# Multiplexers.net
KiCad netlist of a schematic drawn in Altium Designer
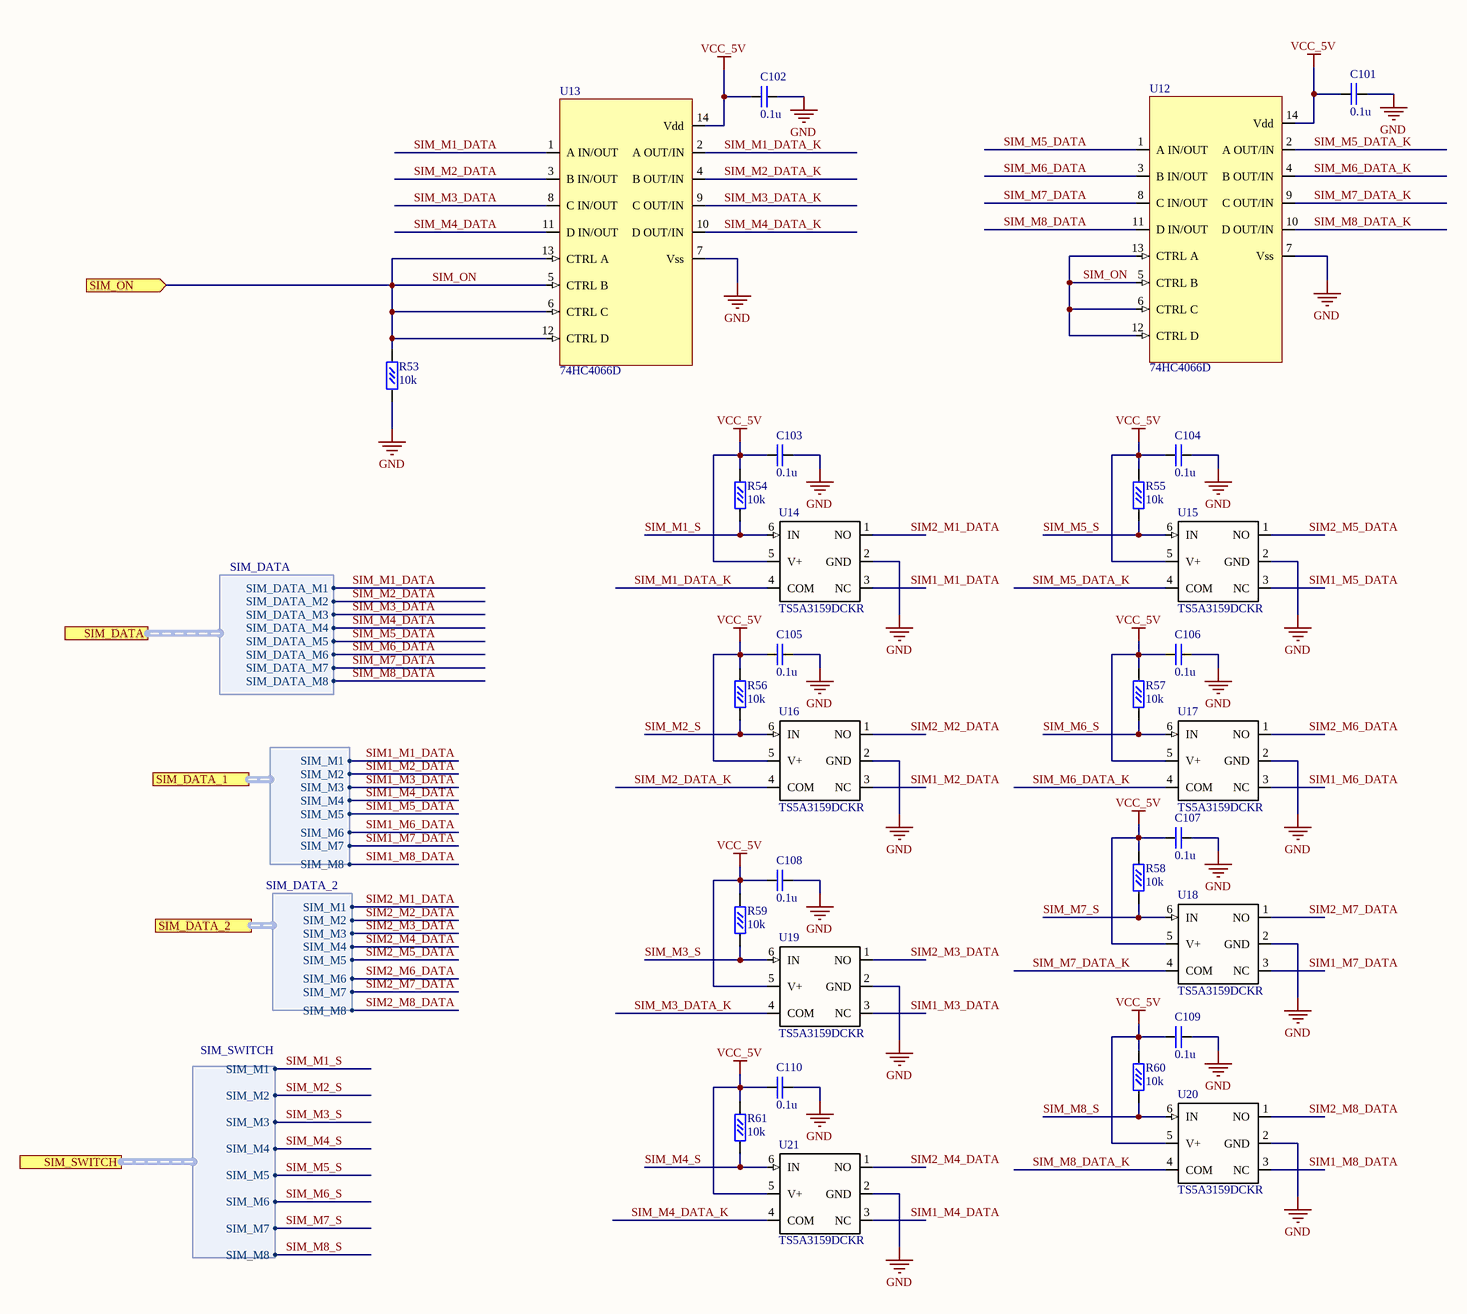
[diagram p0: Multiplexers.SchDoc]

(export (version "E")
  (design (tool "Eeschema 10.0.6"))
  (components
    (comp (ref "C101")
      (value "0.1u")
      (footprint "C0402")
      (description "Chip Capacitor 0402")
      (fields (field (name "VOLTAGE") "16В") (field (name "TOLERANCE") "10%"))
      (libsource (lib "Passives") (part "C0402"))
    )
    (comp (ref "C102")
      (value "0.1u")
      (footprint "C0402")
      (description "Chip Capacitor 0402")
      (fields (field (name "VOLTAGE") "16В") (field (name "TOLERANCE") "10%"))
      (libsource (lib "Passives") (part "C0402"))
    )
    (comp (ref "C103")
      (value "0.1u")
      (footprint "SMD_components:C0402")
      (description "Chip Capacitor 0402")
      (fields (field (name "VOLTAGE") "25В") (field (name "TOLERANCE") "10%"))
      (libsource (lib "Passives") (part "C0402"))
    )
    (comp (ref "C104")
      (value "0.1u")
      (footprint "SMD_components:C0402")
      (description "Chip Capacitor 0402")
      (fields (field (name "VOLTAGE") "25В") (field (name "TOLERANCE") "10%"))
      (libsource (lib "Passives") (part "C0402"))
    )
    (comp (ref "C105")
      (value "0.1u")
      (footprint "SMD_components:C0402")
      (description "Chip Capacitor 0402")
      (fields (field (name "VOLTAGE") "25В") (field (name "TOLERANCE") "10%"))
      (libsource (lib "Passives") (part "C0402"))
    )
    (comp (ref "C106")
      (value "0.1u")
      (footprint "SMD_components:C0402")
      (description "Chip Capacitor 0402")
      (fields (field (name "VOLTAGE") "25В") (field (name "TOLERANCE") "10%"))
      (libsource (lib "Passives") (part "C0402"))
    )
    (comp (ref "C107")
      (value "0.1u")
      (footprint "SMD_components:C0402")
      (description "Chip Capacitor 0402")
      (fields (field (name "VOLTAGE") "25В") (field (name "TOLERANCE") "10%"))
      (libsource (lib "Passives") (part "C0402"))
    )
    (comp (ref "C108")
      (value "0.1u")
      (footprint "SMD_components:C0402")
      (description "Chip Capacitor 0402")
      (fields (field (name "VOLTAGE") "25В") (field (name "TOLERANCE") "10%"))
      (libsource (lib "Passives") (part "C0402"))
    )
    (comp (ref "C109")
      (value "0.1u")
      (footprint "SMD_components:C0402")
      (description "Chip Capacitor 0402")
      (fields (field (name "VOLTAGE") "25В") (field (name "TOLERANCE") "10%"))
      (libsource (lib "Passives") (part "C0402"))
    )
    (comp (ref "C110")
      (value "0.1u")
      (footprint "SMD_components:C0402")
      (description "Chip Capacitor 0402")
      (fields (field (name "VOLTAGE") "25В") (field (name "TOLERANCE") "10%"))
      (libsource (lib "Passives") (part "C0402"))
    )
    (comp (ref "R53")
      (value "10k")
      (footprint "R0603")
      (description "Chip Resistor 0603, 0.1 W")
      (fields (field (name "POWER") "0.1Вт") (field (name "TOLERANCE") "1%"))
      (libsource (lib "Passives") (part "R0603_0.1"))
    )
    (comp (ref "R54")
      (value "10k")
      (footprint "SMD_components:R0603")
      (description "Chip Resistor 0603, 0.1 W")
      (fields (field (name "POWER") "0.1Вт") (field (name "TOLERANCE") "1%"))
      (libsource (lib "Passives") (part "R0603_0.1"))
    )
    (comp (ref "R55")
      (value "10k")
      (footprint "SMD_components:R0603")
      (description "Chip Resistor 0603, 0.1 W")
      (fields (field (name "POWER") "0.1Вт") (field (name "TOLERANCE") "1%"))
      (libsource (lib "Passives") (part "R0603_0.1"))
    )
    (comp (ref "R56")
      (value "10k")
      (footprint "SMD_components:R0603")
      (description "Chip Resistor 0603, 0.1 W")
      (fields (field (name "POWER") "0.1Вт") (field (name "TOLERANCE") "1%"))
      (libsource (lib "Passives") (part "R0603_0.1"))
    )
    (comp (ref "R57")
      (value "10k")
      (footprint "SMD_components:R0603")
      (description "Chip Resistor 0603, 0.1 W")
      (fields (field (name "POWER") "0.1Вт") (field (name "TOLERANCE") "1%"))
      (libsource (lib "Passives") (part "R0603_0.1"))
    )
    (comp (ref "R58")
      (value "10k")
      (footprint "SMD_components:R0603")
      (description "Chip Resistor 0603, 0.1 W")
      (fields (field (name "POWER") "0.1Вт") (field (name "TOLERANCE") "1%"))
      (libsource (lib "Passives") (part "R0603_0.1"))
    )
    (comp (ref "R59")
      (value "10k")
      (footprint "SMD_components:R0603")
      (description "Chip Resistor 0603, 0.1 W")
      (fields (field (name "POWER") "0.1Вт") (field (name "TOLERANCE") "1%"))
      (libsource (lib "Passives") (part "R0603_0.1"))
    )
    (comp (ref "R60")
      (value "10k")
      (footprint "SMD_components:R0603")
      (description "Chip Resistor 0603, 0.1 W")
      (fields (field (name "POWER") "0.1Вт") (field (name "TOLERANCE") "1%"))
      (libsource (lib "Passives") (part "R0603_0.1"))
    )
    (comp (ref "R61")
      (value "10k")
      (footprint "SMD_components:R0603")
      (description "Chip Resistor 0603, 0.1 W")
      (fields (field (name "POWER") "0.1Вт") (field (name "TOLERANCE") "1%"))
      (libsource (lib "Passives") (part "R0603_0.1"))
    )
    (comp (ref "U12")
      (value "74HC4066D")
      (footprint "14-SOIC")
      (description "CMOS QUAD BILATERAL SWITCH")
      (fields (field (name "MANUFACTURER") "Nexperia"))
      (libsource (lib "IC") (part "74HC4066D"))
    )
    (comp (ref "U13")
      (value "74HC4066D")
      (footprint "14-SOIC")
      (description "CMOS QUAD BILATERAL SWITCH")
      (fields (field (name "MANUFACTURER") "Nexperia"))
      (libsource (lib "IC") (part "74HC4066D"))
    )
    (comp (ref "U14")
      (value "TS5A3159")
      (footprint "SC70-6")
      (description "Analog SPDT Switch")
      (fields (field (name "MANUFACTURER") "Texas Instruments") (field (name "PARTNUMBER") "TS5A3159DCKR"))
      (libsource (lib "IC") (part "TS5A3159"))
    )
    (comp (ref "U15")
      (value "TS5A3159")
      (footprint "SC70-6")
      (description "Analog SPDT Switch")
      (fields (field (name "MANUFACTURER") "Texas Instruments") (field (name "PARTNUMBER") "TS5A3159DCKR"))
      (libsource (lib "IC") (part "TS5A3159"))
    )
    (comp (ref "U16")
      (value "TS5A3159")
      (footprint "SC70-6")
      (description "Analog SPDT Switch")
      (fields (field (name "MANUFACTURER") "Texas Instruments") (field (name "PARTNUMBER") "TS5A3159DCKR"))
      (libsource (lib "IC") (part "TS5A3159"))
    )
    (comp (ref "U17")
      (value "TS5A3159")
      (footprint "SC70-6")
      (description "Analog SPDT Switch")
      (fields (field (name "MANUFACTURER") "Texas Instruments") (field (name "PARTNUMBER") "TS5A3159DCKR"))
      (libsource (lib "IC") (part "TS5A3159"))
    )
    (comp (ref "U18")
      (value "TS5A3159")
      (footprint "SC70-6")
      (description "Analog SPDT Switch")
      (fields (field (name "MANUFACTURER") "Texas Instruments") (field (name "PARTNUMBER") "TS5A3159DCKR"))
      (libsource (lib "IC") (part "TS5A3159"))
    )
    (comp (ref "U19")
      (value "TS5A3159")
      (footprint "SC70-6")
      (description "Analog SPDT Switch")
      (fields (field (name "MANUFACTURER") "Texas Instruments") (field (name "PARTNUMBER") "TS5A3159DCKR"))
      (libsource (lib "IC") (part "TS5A3159"))
    )
    (comp (ref "U20")
      (value "TS5A3159")
      (footprint "SC70-6")
      (description "Analog SPDT Switch")
      (fields (field (name "MANUFACTURER") "Texas Instruments") (field (name "PARTNUMBER") "TS5A3159DCKR"))
      (libsource (lib "IC") (part "TS5A3159"))
    )
    (comp (ref "U21")
      (value "TS5A3159")
      (footprint "SC70-6")
      (description "Analog SPDT Switch")
      (fields (field (name "MANUFACTURER") "Texas Instruments") (field (name "PARTNUMBER") "TS5A3159DCKR"))
      (libsource (lib "IC") (part "TS5A3159"))
    )
  )
  (nets
    (net (code "5") (name "/SIM1_M1_DATA") (class "Default")
      (node (ref "U14") (pin "3") (pinfunction "NC_3") (pintype "passive"))
    )
    (net (code "6") (name "/SIM1_M2_DATA") (class "Default")
      (node (ref "U16") (pin "3") (pinfunction "NC_3") (pintype "passive"))
    )
    (net (code "7") (name "/SIM1_M3_DATA") (class "Default")
      (node (ref "U19") (pin "3") (pinfunction "NC_3") (pintype "passive"))
    )
    (net (code "8") (name "/SIM1_M4_DATA") (class "Default")
      (node (ref "U21") (pin "3") (pinfunction "NC_3") (pintype "passive"))
    )
    (net (code "9") (name "/SIM1_M5_DATA") (class "Default")
      (node (ref "U15") (pin "3") (pinfunction "NC_3") (pintype "passive"))
    )
    (net (code "10") (name "/SIM1_M6_DATA") (class "Default")
      (node (ref "U17") (pin "3") (pinfunction "NC_3") (pintype "passive"))
    )
    (net (code "11") (name "/SIM1_M7_DATA") (class "Default")
      (node (ref "U18") (pin "3") (pinfunction "NC_3") (pintype "passive"))
    )
    (net (code "12") (name "/SIM1_M8_DATA") (class "Default")
      (node (ref "U20") (pin "3") (pinfunction "NC_3") (pintype "passive"))
    )
    (net (code "13") (name "/SIM2_M1_DATA") (class "Default")
      (node (ref "U14") (pin "1") (pinfunction "NO_1") (pintype "passive"))
    )
    (net (code "14") (name "/SIM2_M2_DATA") (class "Default")
      (node (ref "U16") (pin "1") (pinfunction "NO_1") (pintype "passive"))
    )
    (net (code "15") (name "/SIM2_M3_DATA") (class "Default")
      (node (ref "U19") (pin "1") (pinfunction "NO_1") (pintype "passive"))
    )
    (net (code "16") (name "/SIM2_M4_DATA") (class "Default")
      (node (ref "U21") (pin "1") (pinfunction "NO_1") (pintype "passive"))
    )
    (net (code "17") (name "/SIM2_M5_DATA") (class "Default")
      (node (ref "U15") (pin "1") (pinfunction "NO_1") (pintype "passive"))
    )
    (net (code "18") (name "/SIM2_M6_DATA") (class "Default")
      (node (ref "U17") (pin "1") (pinfunction "NO_1") (pintype "passive"))
    )
    (net (code "19") (name "/SIM2_M7_DATA") (class "Default")
      (node (ref "U18") (pin "1") (pinfunction "NO_1") (pintype "passive"))
    )
    (net (code "20") (name "/SIM2_M8_DATA") (class "Default")
      (node (ref "U20") (pin "1") (pinfunction "NO_1") (pintype "passive"))
    )
    (net (code "21") (name "/SIM_M1_DATA") (class "Default")
      (node (ref "U13") (pin "1") (pinfunction "A_IN/OUT_1") (pintype "bidirectional"))
    )
    (net (code "22") (name "/SIM_M1_DATA_K") (class "Default")
      (node (ref "U13") (pin "2") (pinfunction "A_OUT/IN_2") (pintype "bidirectional"))
      (node (ref "U14") (pin "4") (pinfunction "COM_4") (pintype "passive"))
    )
    (net (code "23") (name "/SIM_M1_S") (class "Default")
      (node (ref "R54") (pin "1") (pinfunction "1_1") (pintype "passive"))
      (node (ref "U14") (pin "6") (pinfunction "IN_6") (pintype "input"))
    )
    (net (code "24") (name "/SIM_M2_DATA") (class "Default")
      (node (ref "U13") (pin "3") (pinfunction "B_IN/OUT_3") (pintype "bidirectional"))
    )
    (net (code "25") (name "/SIM_M2_DATA_K") (class "Default")
      (node (ref "U13") (pin "4") (pinfunction "B_OUT/IN_4") (pintype "bidirectional"))
      (node (ref "U16") (pin "4") (pinfunction "COM_4") (pintype "passive"))
    )
    (net (code "26") (name "/SIM_M2_S") (class "Default")
      (node (ref "R56") (pin "1") (pinfunction "1_1") (pintype "passive"))
      (node (ref "U16") (pin "6") (pinfunction "IN_6") (pintype "input"))
    )
    (net (code "27") (name "/SIM_M3_DATA") (class "Default")
      (node (ref "U13") (pin "8") (pinfunction "C_IN/OUT_8") (pintype "bidirectional"))
    )
    (net (code "28") (name "/SIM_M3_DATA_K") (class "Default")
      (node (ref "U13") (pin "9") (pinfunction "C_OUT/IN_9") (pintype "bidirectional"))
      (node (ref "U19") (pin "4") (pinfunction "COM_4") (pintype "passive"))
    )
    (net (code "29") (name "/SIM_M3_S") (class "Default")
      (node (ref "R59") (pin "1") (pinfunction "1_1") (pintype "passive"))
      (node (ref "U19") (pin "6") (pinfunction "IN_6") (pintype "input"))
    )
    (net (code "30") (name "/SIM_M4_DATA") (class "Default")
      (node (ref "U13") (pin "11") (pinfunction "D_IN/OUT_11") (pintype "bidirectional"))
    )
    (net (code "31") (name "/SIM_M4_DATA_K") (class "Default")
      (node (ref "U13") (pin "10") (pinfunction "D_OUT/IN_10") (pintype "bidirectional"))
      (node (ref "U21") (pin "4") (pinfunction "COM_4") (pintype "passive"))
    )
    (net (code "32") (name "/SIM_M4_S") (class "Default")
      (node (ref "R61") (pin "1") (pinfunction "1_1") (pintype "passive"))
      (node (ref "U21") (pin "6") (pinfunction "IN_6") (pintype "input"))
    )
    (net (code "33") (name "/SIM_M5_DATA") (class "Default")
      (node (ref "U12") (pin "1") (pinfunction "A_IN/OUT_1") (pintype "bidirectional"))
    )
    (net (code "34") (name "/SIM_M5_DATA_K") (class "Default")
      (node (ref "U12") (pin "2") (pinfunction "A_OUT/IN_2") (pintype "bidirectional"))
      (node (ref "U15") (pin "4") (pinfunction "COM_4") (pintype "passive"))
    )
    (net (code "35") (name "/SIM_M5_S") (class "Default")
      (node (ref "R55") (pin "1") (pinfunction "1_1") (pintype "passive"))
      (node (ref "U15") (pin "6") (pinfunction "IN_6") (pintype "input"))
    )
    (net (code "36") (name "/SIM_M6_DATA") (class "Default")
      (node (ref "U12") (pin "3") (pinfunction "B_IN/OUT_3") (pintype "bidirectional"))
    )
    (net (code "37") (name "/SIM_M6_DATA_K") (class "Default")
      (node (ref "U12") (pin "4") (pinfunction "B_OUT/IN_4") (pintype "bidirectional"))
      (node (ref "U17") (pin "4") (pinfunction "COM_4") (pintype "passive"))
    )
    (net (code "38") (name "/SIM_M6_S") (class "Default")
      (node (ref "R57") (pin "1") (pinfunction "1_1") (pintype "passive"))
      (node (ref "U17") (pin "6") (pinfunction "IN_6") (pintype "input"))
    )
    (net (code "39") (name "/SIM_M7_DATA") (class "Default")
      (node (ref "U12") (pin "8") (pinfunction "C_IN/OUT_8") (pintype "bidirectional"))
    )
    (net (code "40") (name "/SIM_M7_DATA_K") (class "Default")
      (node (ref "U12") (pin "9") (pinfunction "C_OUT/IN_9") (pintype "bidirectional"))
      (node (ref "U18") (pin "4") (pinfunction "COM_4") (pintype "passive"))
    )
    (net (code "41") (name "/SIM_M7_S") (class "Default")
      (node (ref "R58") (pin "1") (pinfunction "1_1") (pintype "passive"))
      (node (ref "U18") (pin "6") (pinfunction "IN_6") (pintype "input"))
    )
    (net (code "42") (name "/SIM_M8_DATA") (class "Default")
      (node (ref "U12") (pin "11") (pinfunction "D_IN/OUT_11") (pintype "bidirectional"))
    )
    (net (code "43") (name "/SIM_M8_DATA_K") (class "Default")
      (node (ref "U12") (pin "10") (pinfunction "D_OUT/IN_10") (pintype "bidirectional"))
      (node (ref "U20") (pin "4") (pinfunction "COM_4") (pintype "passive"))
    )
    (net (code "44") (name "/SIM_M8_S") (class "Default")
      (node (ref "R60") (pin "1") (pinfunction "1_1") (pintype "passive"))
      (node (ref "U20") (pin "6") (pinfunction "IN_6") (pintype "input"))
    )
    (net (code "45") (name "/SIM_ON") (class "Default")
      (node (ref "R53") (pin "2") (pinfunction "2_2") (pintype "passive"))
      (node (ref "U12") (pin "12") (pinfunction "CTRL_D_12") (pintype "input"))
      (node (ref "U12") (pin "13") (pinfunction "CTRL_A_13") (pintype "input"))
      (node (ref "U12") (pin "5") (pinfunction "CTRL_B_5") (pintype "input"))
      (node (ref "U12") (pin "6") (pinfunction "CTRL_C_6") (pintype "input"))
      (node (ref "U13") (pin "12") (pinfunction "CTRL_D_12") (pintype "input"))
      (node (ref "U13") (pin "13") (pinfunction "CTRL_A_13") (pintype "input"))
      (node (ref "U13") (pin "5") (pinfunction "CTRL_B_5") (pintype "input"))
      (node (ref "U13") (pin "6") (pinfunction "CTRL_C_6") (pintype "input"))
    )
    (net (code "50") (name "GND") (class "Default")
      (node (ref "C101") (pin "2") (pinfunction "2_2") (pintype "passive"))
      (node (ref "C102") (pin "2") (pinfunction "2_2") (pintype "passive"))
      (node (ref "C103") (pin "2") (pinfunction "2_2") (pintype "passive"))
      (node (ref "C104") (pin "2") (pinfunction "2_2") (pintype "passive"))
      (node (ref "C105") (pin "2") (pinfunction "2_2") (pintype "passive"))
      (node (ref "C106") (pin "2") (pinfunction "2_2") (pintype "passive"))
      (node (ref "C107") (pin "2") (pinfunction "2_2") (pintype "passive"))
      (node (ref "C108") (pin "2") (pinfunction "2_2") (pintype "passive"))
      (node (ref "C109") (pin "2") (pinfunction "2_2") (pintype "passive"))
      (node (ref "C110") (pin "2") (pinfunction "2_2") (pintype "passive"))
      (node (ref "R53") (pin "1") (pinfunction "1_1") (pintype "passive"))
      (node (ref "U12") (pin "7") (pinfunction "Vss_7") (pintype "power_in"))
      (node (ref "U13") (pin "7") (pinfunction "Vss_7") (pintype "power_in"))
      (node (ref "U14") (pin "2") (pinfunction "GND_2") (pintype "power_in"))
      (node (ref "U15") (pin "2") (pinfunction "GND_2") (pintype "power_in"))
      (node (ref "U16") (pin "2") (pinfunction "GND_2") (pintype "power_in"))
      (node (ref "U17") (pin "2") (pinfunction "GND_2") (pintype "power_in"))
      (node (ref "U18") (pin "2") (pinfunction "GND_2") (pintype "power_in"))
      (node (ref "U19") (pin "2") (pinfunction "GND_2") (pintype "power_in"))
      (node (ref "U20") (pin "2") (pinfunction "GND_2") (pintype "power_in"))
      (node (ref "U21") (pin "2") (pinfunction "GND_2") (pintype "power_in"))
    )
    (net (code "51") (name "VCC_5V") (class "Default")
      (node (ref "C101") (pin "1") (pinfunction "1_1") (pintype "passive"))
      (node (ref "C102") (pin "1") (pinfunction "1_1") (pintype "passive"))
      (node (ref "C103") (pin "1") (pinfunction "1_1") (pintype "passive"))
      (node (ref "C104") (pin "1") (pinfunction "1_1") (pintype "passive"))
      (node (ref "C105") (pin "1") (pinfunction "1_1") (pintype "passive"))
      (node (ref "C106") (pin "1") (pinfunction "1_1") (pintype "passive"))
      (node (ref "C107") (pin "1") (pinfunction "1_1") (pintype "passive"))
      (node (ref "C108") (pin "1") (pinfunction "1_1") (pintype "passive"))
      (node (ref "C109") (pin "1") (pinfunction "1_1") (pintype "passive"))
      (node (ref "C110") (pin "1") (pinfunction "1_1") (pintype "passive"))
      (node (ref "R54") (pin "2") (pinfunction "2_2") (pintype "passive"))
      (node (ref "R55") (pin "2") (pinfunction "2_2") (pintype "passive"))
      (node (ref "R56") (pin "2") (pinfunction "2_2") (pintype "passive"))
      (node (ref "R57") (pin "2") (pinfunction "2_2") (pintype "passive"))
      (node (ref "R58") (pin "2") (pinfunction "2_2") (pintype "passive"))
      (node (ref "R59") (pin "2") (pinfunction "2_2") (pintype "passive"))
      (node (ref "R60") (pin "2") (pinfunction "2_2") (pintype "passive"))
      (node (ref "R61") (pin "2") (pinfunction "2_2") (pintype "passive"))
      (node (ref "U12") (pin "14") (pinfunction "Vdd_14") (pintype "power_in"))
      (node (ref "U13") (pin "14") (pinfunction "Vdd_14") (pintype "power_in"))
      (node (ref "U14") (pin "5") (pinfunction "V+_5") (pintype "power_in"))
      (node (ref "U15") (pin "5") (pinfunction "V+_5") (pintype "power_in"))
      (node (ref "U16") (pin "5") (pinfunction "V+_5") (pintype "power_in"))
      (node (ref "U17") (pin "5") (pinfunction "V+_5") (pintype "power_in"))
      (node (ref "U18") (pin "5") (pinfunction "V+_5") (pintype "power_in"))
      (node (ref "U19") (pin "5") (pinfunction "V+_5") (pintype "power_in"))
      (node (ref "U20") (pin "5") (pinfunction "V+_5") (pintype "power_in"))
      (node (ref "U21") (pin "5") (pinfunction "V+_5") (pintype "power_in"))
    )
  )
)
